# 4_BUTTONS.net
KiCad netlist of a schematic drawn in Altium Designer
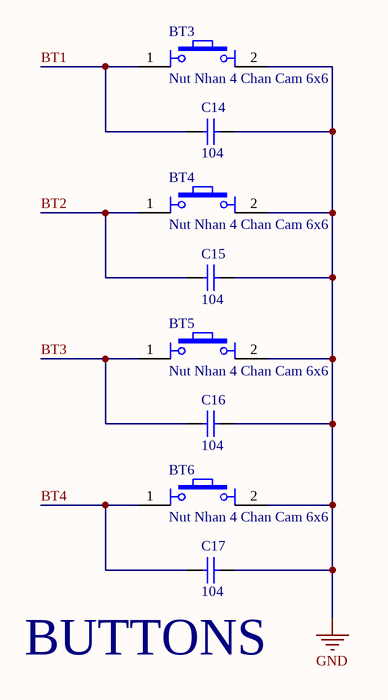
[diagram p0: 4_BUTTONS.SchDoc]

(export (version "E")
  (design (tool "Eeschema 10.0.6"))
  (components
    (comp (ref "BT3")
      (value "Nut Nhan 4 Chan Cam 6x6")
      (footprint "Nut Nhan 4 Chan Cam 6x6")
      (description "Nut Nhan 4 Chan 6x6mm")
      (libsource (lib "Altium_Lib_by_KhueNguyenCreator") (part "Nut Nhan 4 Chan Cam 6x6"))
    )
    (comp (ref "BT4")
      (value "Nut Nhan 4 Chan Cam 6x6")
      (footprint "Nut Nhan 4 Chan Cam 6x6")
      (description "Nut Nhan 4 Chan 6x6mm")
      (libsource (lib "Altium_Lib_by_KhueNguyenCreator") (part "Nut Nhan 4 Chan Cam 6x6"))
    )
    (comp (ref "BT5")
      (value "Nut Nhan 4 Chan Cam 6x6")
      (footprint "Nut Nhan 4 Chan Cam 6x6")
      (description "Nut Nhan 4 Chan 6x6mm")
      (libsource (lib "Altium_Lib_by_KhueNguyenCreator") (part "Nut Nhan 4 Chan Cam 6x6"))
    )
    (comp (ref "BT6")
      (value "Nut Nhan 4 Chan Cam 6x6")
      (footprint "Nut Nhan 4 Chan Cam 6x6")
      (description "Nut Nhan 4 Chan 6x6mm")
      (libsource (lib "Altium_Lib_by_KhueNguyenCreator") (part "Nut Nhan 4 Chan Cam 6x6"))
    )
    (comp (ref "C14")
      (value "104")
      (footprint "tu 0603")
      (description "Dán")
      (libsource (lib "Altium_Lib_by_KhueNguyenCreator") (part "Tu 0603 104 50V 10%"))
    )
    (comp (ref "C15")
      (value "104")
      (footprint "tu 0603")
      (description "Dán")
      (libsource (lib "Altium_Lib_by_KhueNguyenCreator") (part "Tu 0603 104 50V 10%"))
    )
    (comp (ref "C16")
      (value "104")
      (footprint "tu 0603")
      (description "Dán")
      (libsource (lib "Altium_Lib_by_KhueNguyenCreator") (part "Tu 0603 104 50V 10%"))
    )
    (comp (ref "C17")
      (value "104")
      (footprint "tu 0603")
      (description "Dán")
      (libsource (lib "Altium_Lib_by_KhueNguyenCreator") (part "Tu 0603 104 50V 10%"))
    )
  )
  (nets
    (net (code "1") (name "/BT1") (class "Default")
      (node (ref "BT3") (pin "1") (pintype "passive"))
      (node (ref "C14") (pin "1") (pinfunction "1_1") (pintype "passive"))
    )
    (net (code "2") (name "/BT2") (class "Default")
      (node (ref "BT4") (pin "1") (pintype "passive"))
      (node (ref "C15") (pin "1") (pinfunction "1_1") (pintype "passive"))
    )
    (net (code "3") (name "/BT3") (class "Default")
      (node (ref "BT5") (pin "1") (pintype "passive"))
      (node (ref "C16") (pin "1") (pinfunction "1_1") (pintype "passive"))
    )
    (net (code "4") (name "/BT4") (class "Default")
      (node (ref "BT6") (pin "1") (pintype "passive"))
      (node (ref "C17") (pin "1") (pinfunction "1_1") (pintype "passive"))
    )
    (net (code "5") (name "GND") (class "Default")
      (node (ref "BT3") (pin "2") (pintype "passive"))
      (node (ref "BT4") (pin "2") (pintype "passive"))
      (node (ref "BT5") (pin "2") (pintype "passive"))
      (node (ref "BT6") (pin "2") (pintype "passive"))
      (node (ref "C14") (pin "2") (pinfunction "2_2") (pintype "passive"))
      (node (ref "C15") (pin "2") (pinfunction "2_2") (pintype "passive"))
      (node (ref "C16") (pin "2") (pinfunction "2_2") (pintype "passive"))
      (node (ref "C17") (pin "2") (pinfunction "2_2") (pintype "passive"))
    )
  )
)
